# XT-08_Attenuators.net
KiCad netlist of a schematic drawn in EAGLE
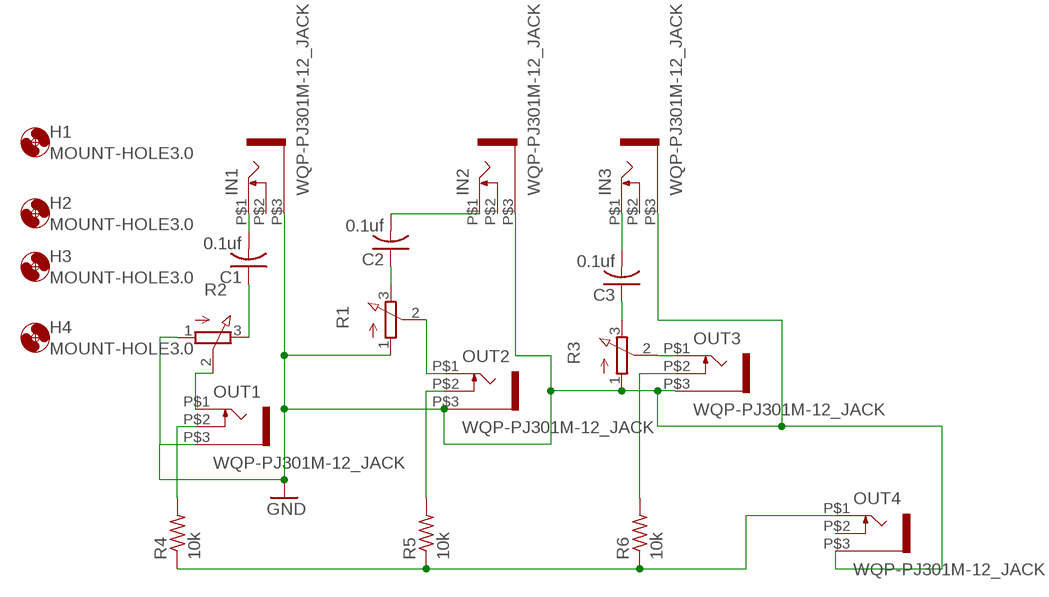
[diagram p0: schematic, sheet 1]

(export (version "E")
  (design (tool "Eeschema 10.0.6"))
  (components
    (comp (ref "C1")
      (value "0.1uf")
      (footprint "eagle-import:C050-025X075")
      (libsource (lib "eagle-import") (part "C-US050-025X075"))
    )
    (comp (ref "C2")
      (value "0.1uf")
      (footprint "eagle-import:C050-025X075")
      (libsource (lib "eagle-import") (part "C-US050-025X075"))
    )
    (comp (ref "C3")
      (value "0.1uf")
      (footprint "eagle-import:C050-025X075")
      (libsource (lib "eagle-import") (part "C-US050-025X075"))
    )
    (comp (ref "H1")
      (value "MOUNT-HOLE3.0")
      (footprint "eagle-import:3,0")
      (libsource (lib "eagle-import") (part "MOUNT-HOLE3.0"))
    )
    (comp (ref "H2")
      (value "MOUNT-HOLE3.0")
      (footprint "eagle-import:3,0")
      (libsource (lib "eagle-import") (part "MOUNT-HOLE3.0"))
    )
    (comp (ref "H3")
      (value "MOUNT-HOLE3.0")
      (footprint "eagle-import:3,0")
      (libsource (lib "eagle-import") (part "MOUNT-HOLE3.0"))
    )
    (comp (ref "H4")
      (value "MOUNT-HOLE3.0")
      (footprint "eagle-import:3,0")
      (libsource (lib "eagle-import") (part "MOUNT-HOLE3.0"))
    )
    (comp (ref "IN1")
      (value "WQP-PJ301M-12_JACK")
      (footprint "eagle-import:WQP-PJ301M-12_JACK")
      (libsource (lib "eagle-import") (part "WQP-PJ301M-12_JACK"))
    )
    (comp (ref "IN2")
      (value "WQP-PJ301M-12_JACK")
      (footprint "eagle-import:WQP-PJ301M-12_JACK")
      (libsource (lib "eagle-import") (part "WQP-PJ301M-12_JACK"))
    )
    (comp (ref "IN3")
      (value "WQP-PJ301M-12_JACK")
      (footprint "eagle-import:WQP-PJ301M-12_JACK")
      (libsource (lib "eagle-import") (part "WQP-PJ301M-12_JACK"))
    )
    (comp (ref "OUT1")
      (value "WQP-PJ301M-12_JACK")
      (footprint "eagle-import:WQP-PJ301M-12_JACK")
      (libsource (lib "eagle-import") (part "WQP-PJ301M-12_JACK"))
    )
    (comp (ref "OUT2")
      (value "WQP-PJ301M-12_JACK")
      (footprint "eagle-import:WQP-PJ301M-12_JACK")
      (libsource (lib "eagle-import") (part "WQP-PJ301M-12_JACK"))
    )
    (comp (ref "OUT3")
      (value "WQP-PJ301M-12_JACK")
      (footprint "eagle-import:WQP-PJ301M-12_JACK")
      (libsource (lib "eagle-import") (part "WQP-PJ301M-12_JACK"))
    )
    (comp (ref "OUT4")
      (value "WQP-PJ301M-12_JACK")
      (footprint "eagle-import:WQP-PJ301M-12_JACK")
      (libsource (lib "eagle-import") (part "WQP-PJ301M-12_JACK"))
    )
    (comp (ref "R1")
      (value "EVUF2L")
      (footprint "eagle-import:EVUFXL")
      (libsource (lib "eagle-import") (part "EVULF2"))
    )
    (comp (ref "R2")
      (value "EVUF2L")
      (footprint "eagle-import:EVUFXL")
      (libsource (lib "eagle-import") (part "EVULF2"))
    )
    (comp (ref "R3")
      (value "EVUF2L")
      (footprint "eagle-import:EVUFXL")
      (libsource (lib "eagle-import") (part "EVULF2"))
    )
    (comp (ref "R4")
      (value "10k")
      (footprint "eagle-import:0204_7")
      (libsource (lib "eagle-import") (part "R-US_0204/7"))
    )
    (comp (ref "R5")
      (value "10k")
      (footprint "eagle-import:0204_7")
      (libsource (lib "eagle-import") (part "R-US_0204/7"))
    )
    (comp (ref "R6")
      (value "10k")
      (footprint "eagle-import:0204_7")
      (libsource (lib "eagle-import") (part "R-US_0204/7"))
    )
  )
  (nets
    (net (code "1") (name "GND") (class "Default")
      (node (ref "IN1") (pin "P$3") (pinfunction "1_P$3") (pintype "passive"))
      (node (ref "IN2") (pin "P$3") (pinfunction "1_P$3") (pintype "passive"))
      (node (ref "IN3") (pin "P$3") (pinfunction "1_P$3") (pintype "passive"))
      (node (ref "OUT1") (pin "P$3") (pinfunction "1_P$3") (pintype "passive"))
      (node (ref "OUT2") (pin "P$3") (pinfunction "1_P$3") (pintype "passive"))
      (node (ref "OUT3") (pin "P$3") (pinfunction "1_P$3") (pintype "passive"))
      (node (ref "OUT4") (pin "P$3") (pinfunction "1_P$3") (pintype "passive"))
      (node (ref "R1") (pin "1") (pinfunction "A_1") (pintype "passive"))
      (node (ref "R2") (pin "1") (pinfunction "A_1") (pintype "passive"))
      (node (ref "R3") (pin "1") (pinfunction "A_1") (pintype "passive"))
    )
    (net (code "2") (name "Net-(IN1-2)") (class "Default")
      (node (ref "C1") (pin "2") (pinfunction "2_2") (pintype "passive"))
      (node (ref "IN1") (pin "P$1") (pinfunction "2_P$1") (pintype "passive"))
    )
    (net (code "3") (name "Net-(IN2-2)") (class "Default")
      (node (ref "C2") (pin "2") (pinfunction "2_2") (pintype "passive"))
      (node (ref "IN2") (pin "P$1") (pinfunction "2_P$1") (pintype "passive"))
    )
    (net (code "4") (name "Net-(IN3-2)") (class "Default")
      (node (ref "C3") (pin "2") (pinfunction "2_2") (pintype "passive"))
      (node (ref "IN3") (pin "P$1") (pinfunction "2_P$1") (pintype "passive"))
    )
    (net (code "5") (name "Net-(OUT1-2)") (class "Default")
      (node (ref "OUT1") (pin "P$1") (pinfunction "2_P$1") (pintype "passive"))
      (node (ref "R2") (pin "2") (pinfunction "S_2") (pintype "passive"))
    )
    (net (code "6") (name "Net-(OUT1-3)") (class "Default")
      (node (ref "OUT1") (pin "P$2") (pinfunction "3_P$2") (pintype "passive"))
      (node (ref "R4") (pin "2") (pinfunction "2_2") (pintype "passive"))
    )
    (net (code "7") (name "Net-(OUT2-2)") (class "Default")
      (node (ref "OUT2") (pin "P$1") (pinfunction "2_P$1") (pintype "passive"))
      (node (ref "R1") (pin "2") (pinfunction "S_2") (pintype "passive"))
    )
    (net (code "8") (name "Net-(OUT2-3)") (class "Default")
      (node (ref "OUT2") (pin "P$2") (pinfunction "3_P$2") (pintype "passive"))
      (node (ref "R5") (pin "2") (pinfunction "2_2") (pintype "passive"))
    )
    (net (code "9") (name "Net-(OUT3-2)") (class "Default")
      (node (ref "OUT3") (pin "P$1") (pinfunction "2_P$1") (pintype "passive"))
      (node (ref "R3") (pin "2") (pinfunction "S_2") (pintype "passive"))
    )
    (net (code "10") (name "Net-(OUT3-3)") (class "Default")
      (node (ref "OUT3") (pin "P$2") (pinfunction "3_P$2") (pintype "passive"))
      (node (ref "R6") (pin "2") (pinfunction "2_2") (pintype "passive"))
    )
    (net (code "11") (name "Net-(OUT4-2)") (class "Default")
      (node (ref "OUT4") (pin "P$1") (pinfunction "2_P$1") (pintype "passive"))
      (node (ref "R4") (pin "1") (pinfunction "1_1") (pintype "passive"))
      (node (ref "R5") (pin "1") (pinfunction "1_1") (pintype "passive"))
      (node (ref "R6") (pin "1") (pinfunction "1_1") (pintype "passive"))
    )
    (net (code "12") (name "Net-(R1-E)") (class "Default")
      (node (ref "C2") (pin "1") (pinfunction "1_1") (pintype "passive"))
      (node (ref "R1") (pin "3") (pinfunction "E_3") (pintype "passive"))
    )
    (net (code "13") (name "Net-(R2-E)") (class "Default")
      (node (ref "C1") (pin "1") (pinfunction "1_1") (pintype "passive"))
      (node (ref "R2") (pin "3") (pinfunction "E_3") (pintype "passive"))
    )
    (net (code "14") (name "Net-(R3-E)") (class "Default")
      (node (ref "C3") (pin "1") (pinfunction "1_1") (pintype "passive"))
      (node (ref "R3") (pin "3") (pinfunction "E_3") (pintype "passive"))
    )
    (net (code "15") (name "unconnected-(IN1-3-PadP$2)") (class "Default")
      (node (ref "IN1") (pin "P$2") (pinfunction "3_P$2") (pintype "passive"))
    )
    (net (code "16") (name "unconnected-(IN2-3-PadP$2)") (class "Default")
      (node (ref "IN2") (pin "P$2") (pinfunction "3_P$2") (pintype "passive"))
    )
    (net (code "17") (name "unconnected-(IN3-3-PadP$2)") (class "Default")
      (node (ref "IN3") (pin "P$2") (pinfunction "3_P$2") (pintype "passive"))
    )
    (net (code "18") (name "unconnected-(OUT4-3-PadP$2)") (class "Default")
      (node (ref "OUT4") (pin "P$2") (pinfunction "3_P$2") (pintype "passive"))
    )
  )
)
